# LCD.net
KiCad netlist of a schematic drawn in Altium Designer
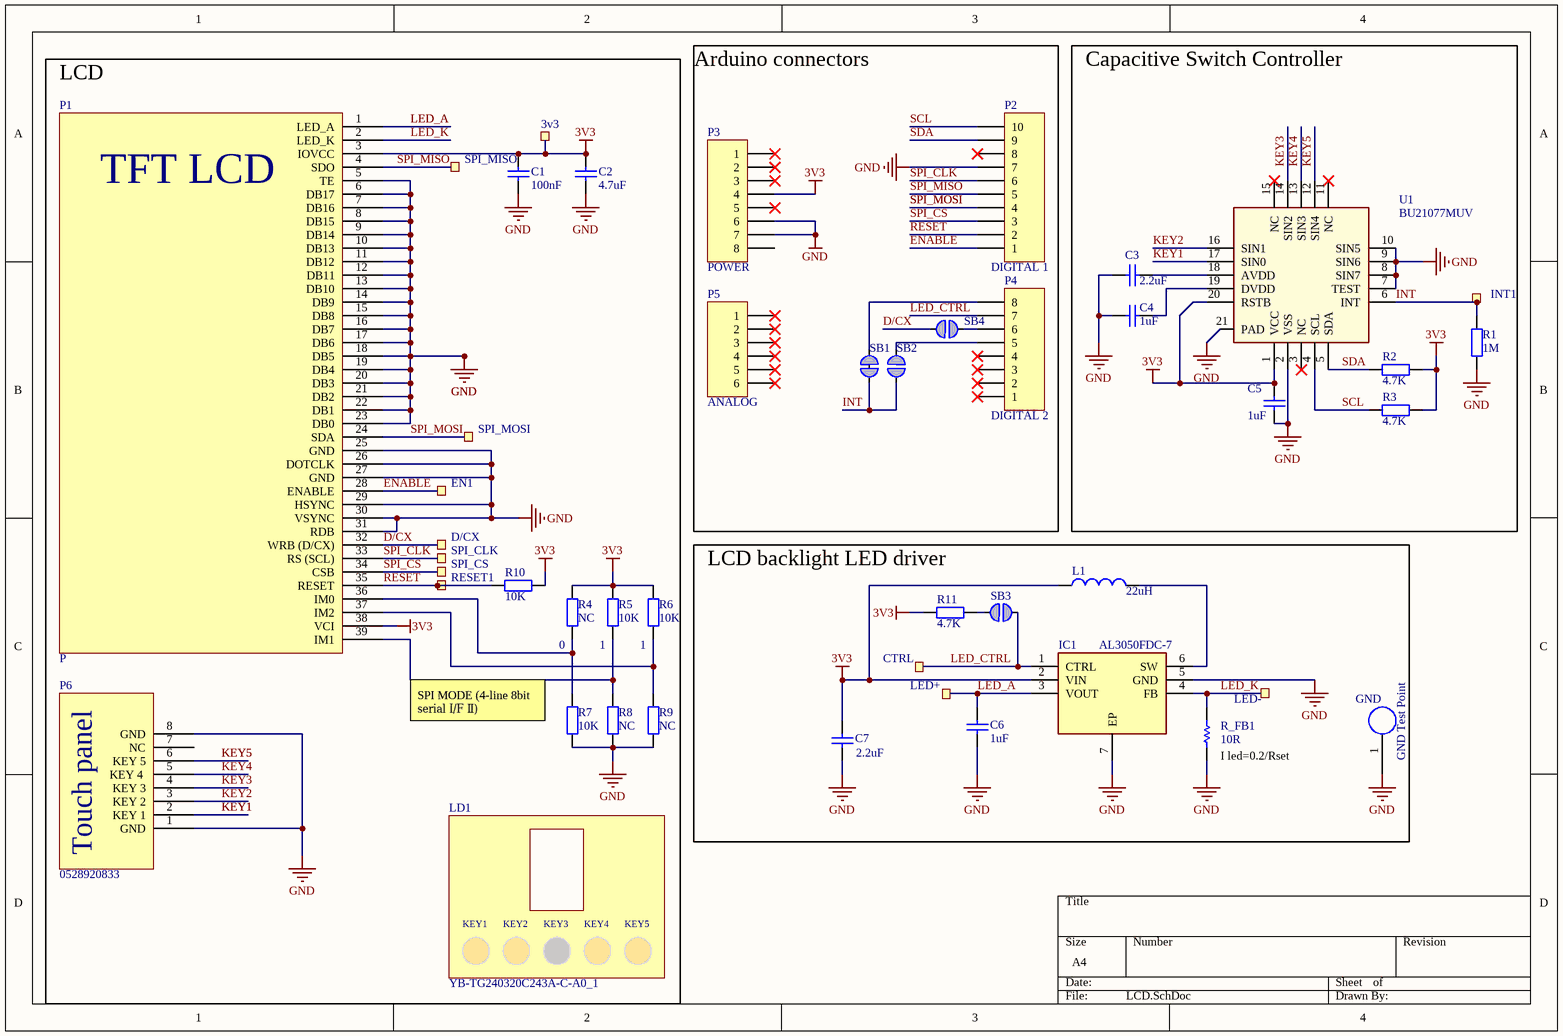
[diagram p0: LCD.SchDoc]

(export (version "E")
  (design (tool "Eeschema 10.0.6"))
  (components
    (comp (ref "3v3")
      (value "Test point")
      (footprint "TP_SMD_Ø1.0mm")
      (description "1.0mm circular SMD testpad")
      (libsource (lib "") (part "TESTPAD_2"))
    )
    (comp (ref "C1")
      (value "100nF")
      (footprint "c0402")
      (description "Capacitor (Semiconductor SIM Model)")
      (fields
        (field (name "MANUFACTURER") "YAGEO")
        (field (name "MANUFACTURER PART NO.") "CC0402KRX7R9BB104")
      )
      (libsource (lib "Miscellaneous Devices") (part "Cap Semi"))
    )
    (comp (ref "C2")
      (value "4.7uF")
      (footprint "c0402")
      (description "Capacitor (Semiconductor SIM Model)")
      (fields
        (field (name "MANUFACTURER") "Samsung")
        (field (name "MANUFACTURER PART NO.") "CL05A475KP5NRNC")
      )
      (libsource (lib "Miscellaneous Devices") (part "Cap Semi"))
    )
    (comp (ref "C3")
      (value "2.2uF")
      (footprint "C0402")
      (description "Capacitor (Semiconductor SIM Model)")
      (fields
        (field (name "MANUFACTURER") "muRata")
        (field (name "MANUFACTURER PART NO.") "GRM155R61A225KE01D")
      )
      (libsource (lib "Miscellaneous Devices") (part "Cap Semi"))
    )
    (comp (ref "C4")
      (value "1uF")
      (footprint "C0402")
      (description "Capacitor (Semiconductor SIM Model)")
      (fields
        (field (name "MANUFACTURER") "muRata")
        (field (name "MANUFACTURER PART NO.") "GRM155R61E105KA12D")
      )
      (libsource (lib "Miscellaneous Devices") (part "Cap Semi"))
    )
    (comp (ref "C5")
      (value "1uF")
      (footprint "C0402")
      (description "Capacitor (Semiconductor SIM Model)")
      (fields
        (field (name "MANUFACTURER") "muRata")
        (field (name "MANUFACTURER PART NO.") "GRM155R61E105KA12D")
      )
      (libsource (lib "Miscellaneous Devices") (part "Cap Semi"))
    )
    (comp (ref "C6")
      (value "1uF")
      (footprint "C0402")
      (description "Capacitor (Semiconductor SIM Model)")
      (fields
        (field (name "MANUFACTURER") "muRata")
        (field (name "MANUFACTURER PART NO.") "GRM155R61E105KA12D")
      )
      (libsource (lib "Miscellaneous Devices") (part "Cap Semi"))
    )
    (comp (ref "C7")
      (value "2.2uF")
      (footprint "C0402")
      (description "Capacitor (Semiconductor SIM Model)")
      (fields
        (field (name "MANUFACTURER") "muRata")
        (field (name "MANUFACTURER PART NO.") "GRM155R61A225KE01D")
      )
      (libsource (lib "Miscellaneous Devices") (part "Cap Semi"))
    )
    (comp (ref "CTRL")
      (value "Test point")
      (footprint "TP_SMD_Ø1.0mm")
      (description "1.0mm circular SMD testpad")
      (libsource (lib "") (part "TESTPAD_1"))
    )
    (comp (ref "D/CX")
      (value "Test point")
      (footprint "TP_SMD_Ø1.0mm")
      (description "1.0mm circular SMD testpad")
      (libsource (lib "Nordic Passive DB") (part "TESTPAD"))
    )
    (comp (ref "EN1")
      (value "Test point")
      (footprint "TP_SMD_Ø1.0mm")
      (description "1.0mm circular SMD testpad")
      (libsource (lib "Nordic Passive DB") (part "TESTPAD"))
    )
    (comp (ref "GND")
      (value "GND Test Point")
      (footprint "5019_keystone")
      (description "SMD Test Point")
      (fields
        (field (name "MANUFACTURER") "Keystone Electrincs")
        (field (name "MANUFACTURER PART NO.") "5019")
      )
      (libsource (lib "test_point") (part "5019"))
    )
    (comp (ref "IC1")
      (value "AL3050FDC-7")
      (footprint "SamacSys:SON65P200X200X61-7N")
      (description "Integrated Circuit")
      (fields (field (name "MANUFACTURER") "Diodes Inc."))
      (libsource (lib "SamacSys") (part "AL3050FDC-7"))
    )
    (comp (ref "INT1")
      (value "Test point")
      (footprint "TP_SMD_Ø1.0mm")
      (description "1.0mm circular SMD testpad")
      (libsource (lib "") (part "TESTPAD_2"))
    )
    (comp (ref "L1")
      (value "22uH")
      (footprint "L2016X12N")
      (description "Inductor")
      (fields
        (field (name "MANUFACTURER") "Chilisin Electronics")
        (field (name "MANUFACTURER PART NO.") "BWVC00201612220M00")
      )
      (libsource (lib "Miscellaneous Devices") (part "Inductor"))
    )
    (comp (ref "LD1")
      (value "YB-TG240320C243A-C-A0_1")
      (footprint "LCD MODULE YB-TG240320C243A-C-A0")
      (fields (field (name "MANUFACTURER") "YEEBO GROUP"))
      (libsource (lib "Schlib1") (part "YB-TG240320C243A-C-A0_1"))
    )
    (comp (ref "LED+")
      (value "Test point")
      (footprint "TP_SMD_Ø1.0mm")
      (description "1.0mm circular SMD testpad")
      (libsource (lib "") (part "TESTPAD_1"))
    )
    (comp (ref "LED-")
      (value "Test point")
      (footprint "TP_SMD_Ø1.0mm")
      (description "1.0mm circular SMD testpad")
      (libsource (lib "Nordic Passive DB") (part "TESTPAD"))
    )
    (comp (ref "P1")
      (value "P")
      (footprint "FPC-39-0.3mm")
      (description "FPC CONNECTOR OF LCD MODULE")
      (fields (field (name "MANUFACTURER") "Molex") (field (name "MANUFACTURER PART NO.") "5035663902"))
      (libsource (lib "Schlib1") (part "P"))
    )
    (comp (ref "P2")
      (value "DIGITAL 1")
      (footprint "Header  10way SMT 2.54mm 1row")
      (fields
        (field (name "MANUFACTURER") "Amphenol ICC")
        (field (name "MANUFACTURER PART NO.") "10129380-910002ALF")
      )
      (libsource (lib "Miscellaneous Connectors") (part "Header 10"))
    )
    (comp (ref "P3")
      (value "POWER")
      (footprint "Header  8way SMT 2.54mm 1row")
      (fields
        (field (name "MANUFACTURER") "Amphenol ICC")
        (field (name "MANUFACTURER PART NO.") "10129380-908002ALF")
      )
      (libsource (lib "") (part "Header 8_1"))
    )
    (comp (ref "P4")
      (value "DIGITAL 2")
      (footprint "Header  8way SMT 2.54mm 1row")
      (fields
        (field (name "MANUFACTURER") "Amphenol ICC")
        (field (name "MANUFACTURER PART NO.") "10129380-908002ALF")
      )
      (libsource (lib "Miscellaneous Connectors") (part "Header 8"))
    )
    (comp (ref "P5")
      (value "ANALOG")
      (footprint "Header  6way SMT 2.54mm 1row")
      (fields
        (field (name "MANUFACTURER") "Amphenol ICC")
        (field (name "MANUFACTURER PART NO.") "10129380-906002BLF")
      )
      (libsource (lib "Miscellaneous Connectors") (part "Header 6"))
    )
    (comp (ref "P6")
      (value "0528920833")
      (footprint "CONN FFC BOTTOM 8POS 0.50MM")
      (description "CONN FFC BOTTOM 8POS 0.50MM R/A")
      (fields (field (name "MANUFACTURER") "Molex"))
      (libsource (lib "Schlib1") (part "0528920833"))
    )
    (comp (ref "R1")
      (value "1M")
      (footprint "R0402")
      (fields (field (name "MANUFACTURER") "ASJ") (field (name "MANUFACTURER PART NO.") "CR10-105-JK"))
      (libsource (lib "") (part "Res2_4"))
    )
    (comp (ref "R2")
      (value "4.7K")
      (footprint "R0402")
      (fields (field (name "MANUFACTURER") "ASJ") (field (name "MANUFACTURER PART NO.") "CR10-472-JK"))
      (libsource (lib "") (part "Res2_1"))
    )
    (comp (ref "R3")
      (value "4.7K")
      (footprint "R0402")
      (fields (field (name "MANUFACTURER") "ASJ") (field (name "MANUFACTURER PART NO.") "CR10-472-JK"))
      (libsource (lib "") (part "Res2_2"))
    )
    (comp (ref "R4")
      (value "NC")
      (footprint "R0402")
      (fields
        (field (name "MANUFACTURER") "ASJ")
        (field (name "MANUFACTURER PART NO.") "CR10-103-JK")
        (field (name "Comment") "Res2")
      )
      (libsource (lib "Miscellaneous Devices") (part "Res2"))
    )
    (comp (ref "R5")
      (value "10K")
      (footprint "R0402")
      (fields (field (name "Comment") "Res2"))
      (libsource (lib "Miscellaneous Devices") (part "Res2"))
    )
    (comp (ref "R6")
      (value "10K")
      (footprint "R0402")
      (fields
        (field (name "MANUFACTURER") "ASJ")
        (field (name "MANUFACTURER PART NO.") "CR10-103-JK")
        (field (name "Comment") "Res2")
      )
      (libsource (lib "Miscellaneous Devices") (part "Res2"))
    )
    (comp (ref "R7")
      (value "10K")
      (footprint "R0402")
      (fields (field (name "Comment") "Res2"))
      (libsource (lib "Miscellaneous Devices") (part "Res2"))
    )
    (comp (ref "R8")
      (value "NC")
      (footprint "R0402")
      (fields
        (field (name "MANUFACTURER") "ASJ")
        (field (name "MANUFACTURER PART NO.") "CR10-103-JK")
        (field (name "Comment") "Res2")
      )
      (libsource (lib "Miscellaneous Devices") (part "Res2"))
    )
    (comp (ref "R9")
      (value "NC")
      (footprint "R0402")
      (fields (field (name "Comment") "Res2"))
      (libsource (lib "") (part "Res2_3"))
    )
    (comp (ref "R10")
      (value "10K")
      (footprint "R0402")
      (fields
        (field (name "MANUFACTURER") "ASJ")
        (field (name "MANUFACTURER PART NO.") "CR10-103-JK")
        (field (name "Comment") "Res2")
      )
      (libsource (lib "") (part "Res2_1"))
    )
    (comp (ref "R11")
      (value "4.7K")
      (footprint "R0402")
      (fields (field (name "MANUFACTURER") "ASJ") (field (name "MANUFACTURER PART NO.") "CR10-472-JK"))
      (libsource (lib "") (part "Res2_1"))
    )
    (comp (ref "RESET1")
      (value "Test point")
      (footprint "TP_SMD_Ø1.0mm")
      (description "1.0mm circular SMD testpad")
      (libsource (lib "Nordic Passive DB") (part "TESTPAD"))
    )
    (comp (ref "R_FB1")
      (value "10R")
      (footprint "R0402")
      (description "Resistor")
      (fields (field (name "MANUFACTURER") "ASJ") (field (name "MANUFACTURER PART NO.") "CR10-10R0-FK"))
      (libsource (lib "Miscellaneous Devices") (part "Res1"))
    )
    (comp (ref "SB1")
      (value "Solderbridge")
      (footprint "Solderbridge_Shorted")
      (description "Shorted Solderbridge")
      (libsource (lib "Nordic Passive DB") (part "SOLDERBRIDGE_SHORTED"))
    )
    (comp (ref "SB2")
      (value "Solderbridge")
      (footprint "Solderbridge")
      (libsource (lib "Nordic Passive DB") (part "SOLDERBRIDGE"))
    )
    (comp (ref "SB3")
      (value "Solderbridge")
      (footprint "Solderbridge")
      (libsource (lib "Nordic Passive DB") (part "SOLDERBRIDGE"))
    )
    (comp (ref "SB4")
      (value "Solderbridge")
      (footprint "Solderbridge")
      (libsource (lib "Nordic Passive DB") (part "SOLDERBRIDGE"))
    )
    (comp (ref "SPI_CLK")
      (value "Test point")
      (footprint "TP_SMD_Ø1.0mm")
      (description "1.0mm circular SMD testpad")
      (libsource (lib "Nordic Passive DB") (part "TESTPAD"))
    )
    (comp (ref "SPI_CS")
      (value "Test point")
      (footprint "TP_SMD_Ø1.0mm")
      (description "1.0mm circular SMD testpad")
      (libsource (lib "Nordic Passive DB") (part "TESTPAD"))
    )
    (comp (ref "SPI_MISO")
      (value "Test point")
      (footprint "TP_SMD_Ø1.0mm")
      (description "1.0mm circular SMD testpad")
      (libsource (lib "Nordic Passive DB") (part "TESTPAD"))
    )
    (comp (ref "SPI_MOSI")
      (value "Test point")
      (footprint "TP_SMD_Ø1.0mm")
      (description "1.0mm circular SMD testpad")
      (libsource (lib "Nordic Passive DB") (part "TESTPAD"))
    )
    (comp (ref "U1")
      (value "BU21077MUV")
      (footprint "VQFN020V4040 - 0.3mm holes")
      (description "Capacitive Switch Controller IC")
      (fields (field (name "MANUFACTURER") "Rohm") (field (name "MANUFACTURER PART NO.") "BU21077MUV-E2"))
      (libsource (lib "Schlib1") (part "BU21077MUV"))
    )
  )
  (nets
    (net (code "1") (name "/D{slash}CX") (class "Default")
      (node (ref "D/CX") (pin "1") (pinfunction "1_1") (pintype "passive"))
      (node (ref "P1") (pin "32") (pinfunction "WRB_(D/CX)_32") (pintype "passive"))
      (node (ref "SB4") (pin "1") (pinfunction "0_1") (pintype "passive"))
    )
    (net (code "2") (name "/ENABLE") (class "Default")
      (node (ref "EN1") (pin "1") (pinfunction "1_1") (pintype "passive"))
      (node (ref "P1") (pin "28") (pinfunction "ENABLE_28") (pintype "passive"))
      (node (ref "P2") (pin "1") (pinfunction "1_1") (pintype "passive"))
    )
    (net (code "3") (name "/INT") (class "Default")
      (node (ref "INT1") (pin "1") (pinfunction "1_1") (pintype "passive"))
      (node (ref "R1") (pin "2") (pinfunction "2_2") (pintype "passive"))
      (node (ref "SB1") (pin "2") (pinfunction "1_2") (pintype "passive"))
      (node (ref "SB2") (pin "2") (pinfunction "1_2") (pintype "passive"))
      (node (ref "U1") (pin "6") (pinfunction "INT_6") (pintype "passive"))
    )
    (net (code "4") (name "/KEY1") (class "Default")
      (node (ref "P6") (pin "2") (pinfunction "KEY_1_2") (pintype "passive"))
      (node (ref "U1") (pin "17") (pinfunction "SIN0_17") (pintype "passive"))
    )
    (net (code "5") (name "/KEY2") (class "Default")
      (node (ref "P6") (pin "3") (pinfunction "KEY_2_3") (pintype "passive"))
      (node (ref "U1") (pin "16") (pinfunction "SIN1_16") (pintype "passive"))
    )
    (net (code "6") (name "/KEY3") (class "Default")
      (node (ref "P6") (pin "4") (pinfunction "KEY_3_4") (pintype "passive"))
      (node (ref "U1") (pin "14") (pinfunction "SIN2_14") (pintype "passive"))
    )
    (net (code "7") (name "/KEY4") (class "Default")
      (node (ref "P6") (pin "5") (pinfunction "KEY_4_5") (pintype "passive"))
      (node (ref "U1") (pin "13") (pinfunction "SIN3_13") (pintype "passive"))
    )
    (net (code "8") (name "/KEY5") (class "Default")
      (node (ref "P6") (pin "6") (pinfunction "KEY_5_6") (pintype "passive"))
      (node (ref "U1") (pin "12") (pinfunction "SIN4_12") (pintype "passive"))
    )
    (net (code "9") (name "/LED_A") (class "Default")
      (node (ref "C6") (pin "1") (pinfunction "1_1") (pintype "passive"))
      (node (ref "IC1") (pin "3") (pinfunction "VOUT_3") (pintype "passive"))
      (node (ref "LED+") (pin "1") (pinfunction "1_1") (pintype "passive"))
      (node (ref "P1") (pin "1") (pinfunction "LED_A_1") (pintype "passive"))
    )
    (net (code "10") (name "/LED_CTRL") (class "Default")
      (node (ref "CTRL") (pin "1") (pinfunction "1_1") (pintype "passive"))
      (node (ref "IC1") (pin "1") (pinfunction "CTRL_1") (pintype "passive"))
      (node (ref "P4") (pin "7") (pinfunction "7_7") (pintype "passive"))
      (node (ref "SB3") (pin "2") (pinfunction "1_2") (pintype "passive"))
    )
    (net (code "11") (name "/LED_K") (class "Default")
      (node (ref "IC1") (pin "4") (pinfunction "FB_4") (pintype "passive"))
      (node (ref "LED-") (pin "1") (pinfunction "1_1") (pintype "passive"))
      (node (ref "P1") (pin "2") (pinfunction "LED_K_2") (pintype "passive"))
      (node (ref "R_FB1") (pin "2") (pinfunction "2_2") (pintype "passive"))
    )
    (net (code "12") (name "/RESET") (class "Default")
      (node (ref "P1") (pin "35") (pinfunction "RESET_35") (pintype "passive"))
      (node (ref "P2") (pin "2") (pinfunction "2_2") (pintype "passive"))
      (node (ref "R10") (pin "1") (pinfunction "1_1") (pintype "passive"))
      (node (ref "RESET1") (pin "1") (pinfunction "1_1") (pintype "passive"))
    )
    (net (code "13") (name "/SCL") (class "Default")
      (node (ref "P2") (pin "10") (pinfunction "10_10") (pintype "passive"))
      (node (ref "R3") (pin "2") (pinfunction "2_2") (pintype "passive"))
      (node (ref "U1") (pin "4") (pinfunction "SCL_4") (pintype "passive"))
    )
    (net (code "14") (name "/SDA") (class "Default")
      (node (ref "P2") (pin "9") (pinfunction "9_9") (pintype "passive"))
      (node (ref "R2") (pin "1") (pinfunction "1_1") (pintype "passive"))
      (node (ref "U1") (pin "5") (pinfunction "SDA_5") (pintype "passive"))
    )
    (net (code "15") (name "/SPI_CLK") (class "Default")
      (node (ref "P1") (pin "33") (pinfunction "RS_(SCL)_33") (pintype "passive"))
      (node (ref "P2") (pin "6") (pinfunction "6_6") (pintype "passive"))
      (node (ref "SPI_CLK") (pin "1") (pinfunction "1_1") (pintype "passive"))
    )
    (net (code "16") (name "/SPI_CS") (class "Default")
      (node (ref "P1") (pin "34") (pinfunction "CSB_34") (pintype "passive"))
      (node (ref "P2") (pin "3") (pinfunction "3_3") (pintype "passive"))
      (node (ref "SPI_CS") (pin "1") (pinfunction "1_1") (pintype "passive"))
    )
    (net (code "17") (name "/SPI_MISO") (class "Default")
      (node (ref "P1") (pin "4") (pinfunction "SDO_4") (pintype "passive"))
      (node (ref "P2") (pin "5") (pinfunction "5_5") (pintype "passive"))
      (node (ref "SPI_MISO") (pin "1") (pinfunction "1_1") (pintype "passive"))
    )
    (net (code "18") (name "/SPI_MOSI") (class "Default")
      (node (ref "P1") (pin "24") (pinfunction "SDA_24") (pintype "passive"))
      (node (ref "P2") (pin "4") (pinfunction "4_4") (pintype "passive"))
      (node (ref "SPI_MOSI") (pin "1") (pinfunction "1_1") (pintype "passive"))
    )
    (net (code "19") (name "3V3") (class "Default")
      (node (ref "3v3") (pin "1") (pinfunction "1_1") (pintype "passive"))
      (node (ref "C1") (pin "2") (pinfunction "2_2") (pintype "passive"))
      (node (ref "C2") (pin "2") (pinfunction "2_2") (pintype "passive"))
      (node (ref "C5") (pin "2") (pinfunction "2_2") (pintype "passive"))
      (node (ref "C7") (pin "1") (pinfunction "1_1") (pintype "passive"))
      (node (ref "IC1") (pin "2") (pinfunction "VIN_2") (pintype "passive"))
      (node (ref "L1") (pin "1") (pinfunction "1_1") (pintype "passive"))
      (node (ref "P1") (pin "3") (pinfunction "IOVCC_3") (pintype "passive"))
      (node (ref "P1") (pin "38") (pinfunction "VCI_38") (pintype "passive"))
      (node (ref "P3") (pin "4") (pinfunction "4_4") (pintype "passive"))
      (node (ref "R10") (pin "2") (pinfunction "2_2") (pintype "passive"))
      (node (ref "R11") (pin "1") (pinfunction "1_1") (pintype "passive"))
      (node (ref "R2") (pin "2") (pinfunction "2_2") (pintype "passive"))
      (node (ref "R3") (pin "1") (pinfunction "1_1") (pintype "passive"))
      (node (ref "R4") (pin "1") (pinfunction "1_1") (pintype "passive"))
      (node (ref "R5") (pin "1") (pinfunction "1_1") (pintype "passive"))
      (node (ref "R6") (pin "1") (pinfunction "1_1") (pintype "passive"))
      (node (ref "U1") (pin "1") (pinfunction "VCC_1") (pintype "passive"))
      (node (ref "U1") (pin "20") (pinfunction "RSTB_20") (pintype "passive"))
    )
    (net (code "20") (name "GND") (class "Default")
      (node (ref "C1") (pin "1") (pinfunction "1_1") (pintype "passive"))
      (node (ref "C2") (pin "1") (pinfunction "1_1") (pintype "passive"))
      (node (ref "C3") (pin "1") (pinfunction "1_1") (pintype "passive"))
      (node (ref "C4") (pin "1") (pinfunction "1_1") (pintype "passive"))
      (node (ref "C5") (pin "1") (pinfunction "1_1") (pintype "passive"))
      (node (ref "C6") (pin "2") (pinfunction "2_2") (pintype "passive"))
      (node (ref "C7") (pin "2") (pinfunction "2_2") (pintype "passive"))
      (node (ref "GND") (pin "1") (pinfunction "1_1") (pintype "passive"))
      (node (ref "IC1") (pin "5") (pinfunction "GND_5") (pintype "passive"))
      (node (ref "IC1") (pin "7") (pinfunction "EP_7") (pintype "passive"))
      (node (ref "P1") (pin "10") (pinfunction "DB13_10") (pintype "passive"))
      (node (ref "P1") (pin "11") (pinfunction "DB12_11") (pintype "passive"))
      (node (ref "P1") (pin "12") (pinfunction "DB11_12") (pintype "passive"))
      (node (ref "P1") (pin "13") (pinfunction "DB10_13") (pintype "passive"))
      (node (ref "P1") (pin "14") (pinfunction "DB9_14") (pintype "passive"))
      (node (ref "P1") (pin "15") (pinfunction "DB8_15") (pintype "passive"))
      (node (ref "P1") (pin "16") (pinfunction "DB7_16") (pintype "passive"))
      (node (ref "P1") (pin "17") (pinfunction "DB6_17") (pintype "passive"))
      (node (ref "P1") (pin "18") (pinfunction "DB5_18") (pintype "passive"))
      (node (ref "P1") (pin "19") (pinfunction "DB4_19") (pintype "passive"))
      (node (ref "P1") (pin "20") (pinfunction "DB3_20") (pintype "passive"))
      (node (ref "P1") (pin "21") (pinfunction "DB2_21") (pintype "passive"))
      (node (ref "P1") (pin "22") (pinfunction "DB1_22") (pintype "passive"))
      (node (ref "P1") (pin "23") (pinfunction "DB0_23") (pintype "passive"))
      (node (ref "P1") (pin "25") (pinfunction "GND_25") (pintype "passive"))
      (node (ref "P1") (pin "26") (pinfunction "DOTCLK_26") (pintype "passive"))
      (node (ref "P1") (pin "27") (pinfunction "GND_27") (pintype "passive"))
      (node (ref "P1") (pin "29") (pinfunction "HSYNC_29") (pintype "passive"))
      (node (ref "P1") (pin "30") (pinfunction "VSYNC_30") (pintype "passive"))
      (node (ref "P1") (pin "31") (pinfunction "RDB_31") (pintype "passive"))
      (node (ref "P1") (pin "5") (pinfunction "TE_5") (pintype "passive"))
      (node (ref "P1") (pin "6") (pinfunction "DB17_6") (pintype "passive"))
      (node (ref "P1") (pin "7") (pinfunction "DB16_7") (pintype "passive"))
      (node (ref "P1") (pin "8") (pinfunction "DB15_8") (pintype "passive"))
      (node (ref "P1") (pin "9") (pinfunction "DB14_9") (pintype "passive"))
      (node (ref "P2") (pin "7") (pinfunction "7_7") (pintype "passive"))
      (node (ref "P3") (pin "6") (pinfunction "6_6") (pintype "passive"))
      (node (ref "P3") (pin "7") (pinfunction "7_7") (pintype "passive"))
      (node (ref "P6") (pin "1") (pinfunction "GND_1") (pintype "passive"))
      (node (ref "P6") (pin "8") (pinfunction "GND_8") (pintype "passive"))
      (node (ref "R1") (pin "1") (pinfunction "1_1") (pintype "passive"))
      (node (ref "R7") (pin "2") (pinfunction "2_2") (pintype "passive"))
      (node (ref "R8") (pin "2") (pinfunction "2_2") (pintype "passive"))
      (node (ref "R9") (pin "1") (pinfunction "1_1") (pintype "passive"))
      (node (ref "R_FB1") (pin "1") (pinfunction "1_1") (pintype "passive"))
      (node (ref "U1") (pin "10") (pinfunction "SIN5_10") (pintype "passive"))
      (node (ref "U1") (pin "2") (pinfunction "VSS_2") (pintype "passive"))
      (node (ref "U1") (pin "21") (pinfunction "PAD_21") (pintype "passive"))
      (node (ref "U1") (pin "7") (pinfunction "TEST_7") (pintype "passive"))
      (node (ref "U1") (pin "8") (pinfunction "SIN7_8") (pintype "passive"))
      (node (ref "U1") (pin "9") (pinfunction "SIN6_9") (pintype "passive"))
    )
    (net (code "21") (name "Net-(IC1-SW)") (class "Default")
      (node (ref "IC1") (pin "6") (pinfunction "SW_6") (pintype "passive"))
      (node (ref "L1") (pin "2") (pinfunction "2_2") (pintype "passive"))
    )
    (net (code "22") (name "Net-(P1-IM0)") (class "Default")
      (node (ref "P1") (pin "36") (pinfunction "IM0_36") (pintype "passive"))
      (node (ref "R4") (pin "2") (pinfunction "2_2") (pintype "passive"))
      (node (ref "R7") (pin "1") (pinfunction "1_1") (pintype "passive"))
    )
    (net (code "23") (name "Net-(P1-IM1)") (class "Default")
      (node (ref "P1") (pin "39") (pinfunction "IM1_39") (pintype "passive"))
      (node (ref "R5") (pin "2") (pinfunction "2_2") (pintype "passive"))
      (node (ref "R8") (pin "1") (pinfunction "1_1") (pintype "passive"))
    )
    (net (code "24") (name "Net-(P1-IM2)") (class "Default")
      (node (ref "P1") (pin "37") (pinfunction "IM2_37") (pintype "passive"))
      (node (ref "R6") (pin "2") (pinfunction "2_2") (pintype "passive"))
      (node (ref "R9") (pin "2") (pinfunction "2_2") (pintype "passive"))
    )
    (net (code "25") (name "Net-(SB1-0)") (class "Default")
      (node (ref "P4") (pin "8") (pinfunction "8_8") (pintype "passive"))
      (node (ref "SB1") (pin "1") (pinfunction "0_1") (pintype "passive"))
    )
    (net (code "26") (name "Net-(SB2-0)") (class "Default")
      (node (ref "P4") (pin "5") (pinfunction "5_5") (pintype "passive"))
      (node (ref "SB2") (pin "1") (pinfunction "0_1") (pintype "passive"))
    )
    (net (code "27") (name "Net-(SB3-0)") (class "Default")
      (node (ref "R11") (pin "2") (pinfunction "2_2") (pintype "passive"))
      (node (ref "SB3") (pin "1") (pinfunction "0_1") (pintype "passive"))
    )
    (net (code "28") (name "Net-(SB4-1)") (class "Default")
      (node (ref "P4") (pin "6") (pinfunction "6_6") (pintype "passive"))
      (node (ref "SB4") (pin "2") (pinfunction "1_2") (pintype "passive"))
    )
    (net (code "29") (name "Net-(U1-AVDD)") (class "Default")
      (node (ref "C3") (pin "2") (pinfunction "2_2") (pintype "passive"))
      (node (ref "U1") (pin "18") (pinfunction "AVDD_18") (pintype "passive"))
    )
    (net (code "30") (name "Net-(U1-DVDD)") (class "Default")
      (node (ref "C4") (pin "2") (pinfunction "2_2") (pintype "passive"))
      (node (ref "U1") (pin "19") (pinfunction "DVDD_19") (pintype "passive"))
    )
    (net (code "31") (name "unconnected-(P2-Pad8)") (class "Default")
      (node (ref "P2") (pin "8") (pinfunction "8_8") (pintype "passive+no_connect"))
    )
    (net (code "32") (name "unconnected-(P3-Pad1)") (class "Default")
      (node (ref "P3") (pin "1") (pinfunction "1_1") (pintype "passive+no_connect"))
    )
    (net (code "33") (name "unconnected-(P3-Pad2)") (class "Default")
      (node (ref "P3") (pin "2") (pinfunction "2_2") (pintype "passive+no_connect"))
    )
    (net (code "34") (name "unconnected-(P3-Pad3)") (class "Default")
      (node (ref "P3") (pin "3") (pinfunction "3_3") (pintype "passive+no_connect"))
    )
    (net (code "35") (name "unconnected-(P3-Pad5)") (class "Default")
      (node (ref "P3") (pin "5") (pinfunction "5_5") (pintype "passive+no_connect"))
    )
    (net (code "36") (name "unconnected-(P3-Pad8)") (class "Default")
      (node (ref "P3") (pin "8") (pinfunction "8_8") (pintype "passive"))
    )
    (net (code "37") (name "unconnected-(P4-Pad1)") (class "Default")
      (node (ref "P4") (pin "1") (pinfunction "1_1") (pintype "passive+no_connect"))
    )
    (net (code "38") (name "unconnected-(P4-Pad2)") (class "Default")
      (node (ref "P4") (pin "2") (pinfunction "2_2") (pintype "passive+no_connect"))
    )
    (net (code "39") (name "unconnected-(P4-Pad3)") (class "Default")
      (node (ref "P4") (pin "3") (pinfunction "3_3") (pintype "passive+no_connect"))
    )
    (net (code "40") (name "unconnected-(P4-Pad4)") (class "Default")
      (node (ref "P4") (pin "4") (pinfunction "4_4") (pintype "passive+no_connect"))
    )
    (net (code "41") (name "unconnected-(P5-Pad1)") (class "Default")
      (node (ref "P5") (pin "1") (pinfunction "1_1") (pintype "passive+no_connect"))
    )
    (net (code "42") (name "unconnected-(P5-Pad2)") (class "Default")
      (node (ref "P5") (pin "2") (pinfunction "2_2") (pintype "passive+no_connect"))
    )
    (net (code "43") (name "unconnected-(P5-Pad3)") (class "Default")
      (node (ref "P5") (pin "3") (pinfunction "3_3") (pintype "passive+no_connect"))
    )
    (net (code "44") (name "unconnected-(P5-Pad4)") (class "Default")
      (node (ref "P5") (pin "4") (pinfunction "4_4") (pintype "passive+no_connect"))
    )
    (net (code "45") (name "unconnected-(P5-Pad5)") (class "Default")
      (node (ref "P5") (pin "5") (pinfunction "5_5") (pintype "passive+no_connect"))
    )
    (net (code "46") (name "unconnected-(P5-Pad6)") (class "Default")
      (node (ref "P5") (pin "6") (pinfunction "6_6") (pintype "passive+no_connect"))
    )
    (net (code "47") (name "unconnected-(P6-NC-Pad7)") (class "Default")
      (node (ref "P6") (pin "7") (pinfunction "NC_7") (pintype "passive"))
    )
    (net (code "48") (name "unconnected-(U1-NC-Pad3)") (class "Default")
      (node (ref "U1") (pin "3") (pinfunction "NC_3") (pintype "passive+no_connect"))
    )
    (net (code "49") (name "unconnected-(U1-NC-Pad11)") (class "Default")
      (node (ref "U1") (pin "11") (pinfunction "NC_11") (pintype "passive+no_connect"))
    )
    (net (code "50") (name "unconnected-(U1-NC-Pad15)") (class "Default")
      (node (ref "U1") (pin "15") (pinfunction "NC_15") (pintype "passive+no_connect"))
    )
  )
)
